# Power.net
KiCad netlist of a schematic drawn in Altium Designer
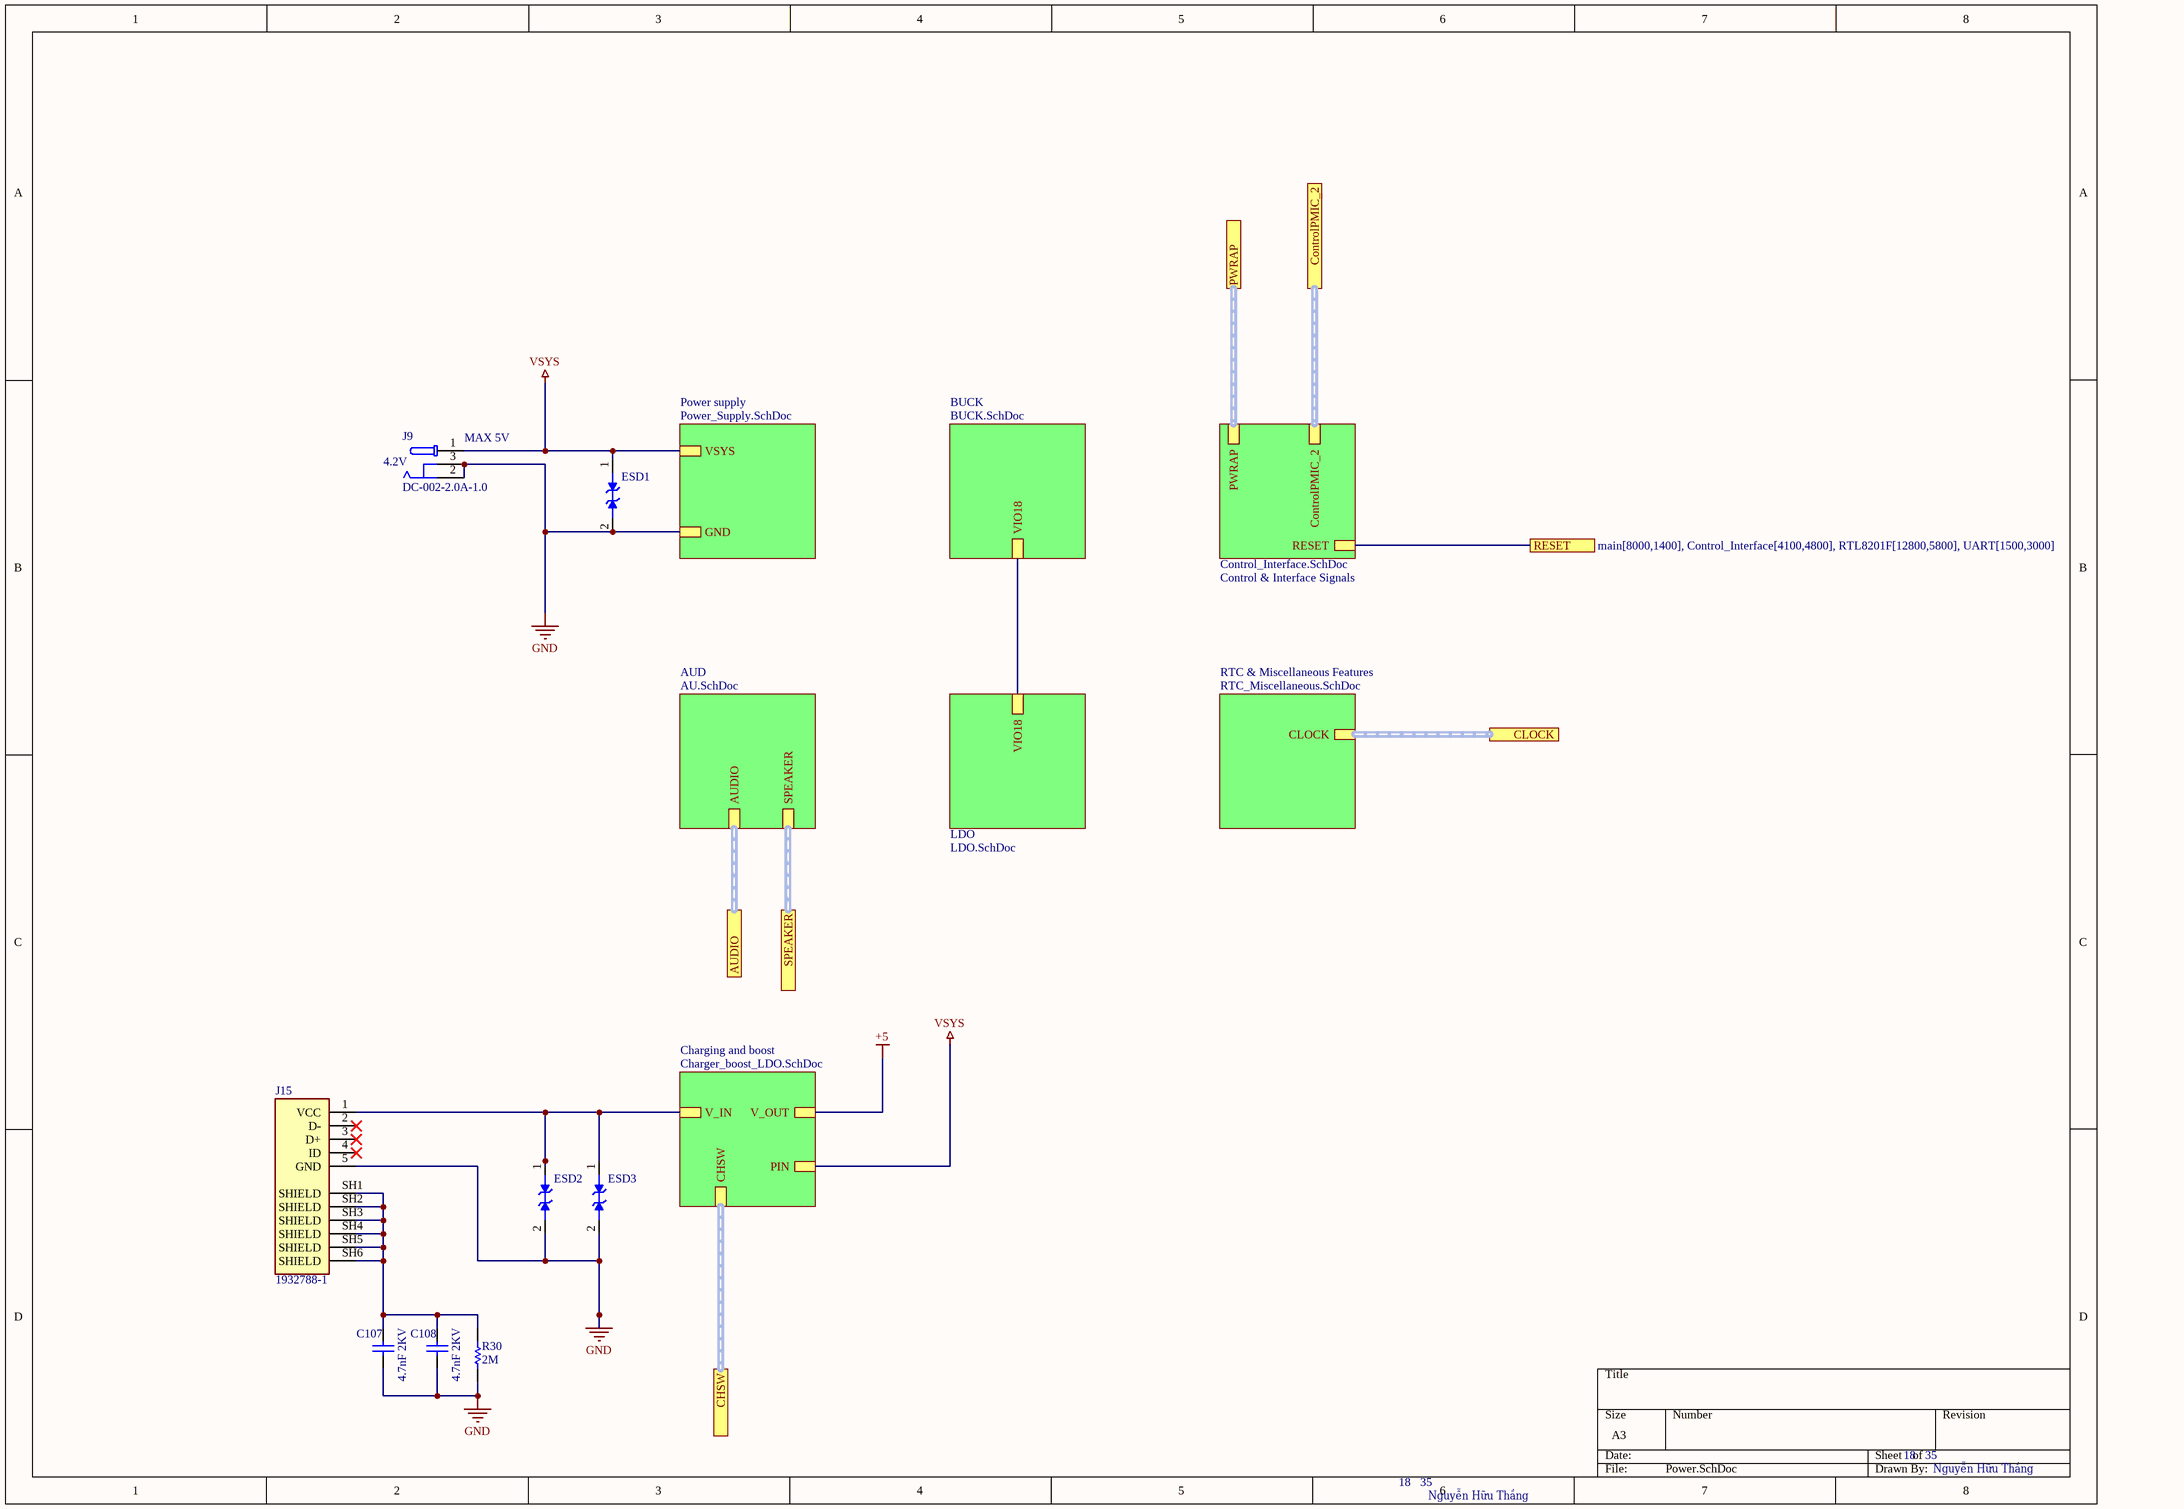
[diagram p0: Power.SchDoc]

(export (version "E")
  (design (tool "Eeschema 10.0.6"))
  (components
    (comp (ref "C107")
      (value "4.7nF 2KV")
      (footprint "C1210")
      (fields (field (name "Comment") "C1210"))
      (libsource (lib "kit") (part "C1210"))
    )
    (comp (ref "C108")
      (value "4.7nF 2KV")
      (footprint "C1210")
      (fields (field (name "Comment") "C1210"))
      (libsource (lib "kit") (part "C1210"))
    )
    (comp (ref "ESD1")
      (value "ESD9B5.0ST5G")
      (footprint "SODFL1006X40N")
      (description "Clamp Ipp Tvs Diode Surface Mount SOD-923")
      (libsource (lib "kit") (part "ESD9B5.0ST5G"))
    )
    (comp (ref "ESD2")
      (value "ESD9B5.0ST5G")
      (footprint "SODFL1006X40N")
      (description "Clamp Ipp Tvs Diode Surface Mount SOD-923")
      (libsource (lib "kit") (part "ESD9B5.0ST5G"))
    )
    (comp (ref "ESD3")
      (value "ESD9B5.0ST5G")
      (footprint "SODFL1006X40N")
      (description "Clamp Ipp Tvs Diode Surface Mount SOD-923")
      (libsource (lib "kit") (part "ESD9B5.0ST5G"))
    )
    (comp (ref "J9")
      (value "DC-002-2.0A-1.0")
      (footprint "DC00220A10")
      (description "Connector")
      (libsource (lib "kit") (part "DC-002-2.0A-1.0"))
    )
    (comp (ref "J15")
      (value "1932788-1")
      (footprint "TE_1932788-1")
      (libsource (lib "kit") (part "1932788-1"))
    )
    (comp (ref "R30")
      (value "2M")
      (footprint "R0603")
      (fields (field (name "Comment") "R0603"))
      (libsource (lib "kit") (part "R0603"))
    )
  )
  (nets
    (net (code "13") (name "/V_IN") (class "Default")
      (node (ref "ESD2") (pin "1") (pinfunction "A_1") (pintype "passive"))
      (node (ref "ESD3") (pin "1") (pinfunction "A_1") (pintype "passive"))
      (node (ref "J15") (pin "1") (pinfunction "VCC_1") (pintype "power_in"))
    )
    (net (code "14") (name "GND") (class "Default")
      (node (ref "C107") (pin "1") (pinfunction "1_1") (pintype "passive"))
      (node (ref "C108") (pin "1") (pinfunction "1_1") (pintype "passive"))
      (node (ref "ESD1") (pin "2") (pinfunction "A1_2") (pintype "passive"))
      (node (ref "ESD2") (pin "2") (pinfunction "A1_2") (pintype "passive"))
      (node (ref "ESD3") (pin "2") (pinfunction "A1_2") (pintype "passive"))
      (node (ref "J15") (pin "5") (pinfunction "GND_5") (pintype "power_in"))
      (node (ref "J9") (pin "2") (pinfunction "2_2") (pintype "passive"))
      (node (ref "J9") (pin "3") (pinfunction "3_3") (pintype "passive"))
      (node (ref "R30") (pin "2") (pinfunction "2_2") (pintype "passive"))
    )
    (net (code "15") (name "Net-(C107-Pad2)") (class "Default")
      (node (ref "C107") (pin "2") (pinfunction "2_2") (pintype "passive"))
      (node (ref "C108") (pin "2") (pinfunction "2_2") (pintype "passive"))
      (node (ref "J15") (pin "SH1") (pinfunction "SHIELD_SH1") (pintype "passive"))
      (node (ref "J15") (pin "SH2") (pinfunction "SHIELD_SH2") (pintype "passive"))
      (node (ref "J15") (pin "SH3") (pinfunction "SHIELD_SH3") (pintype "passive"))
      (node (ref "J15") (pin "SH4") (pinfunction "SHIELD_SH4") (pintype "passive"))
      (node (ref "J15") (pin "SH5") (pinfunction "SHIELD_SH5") (pintype "passive"))
      (node (ref "J15") (pin "SH6") (pinfunction "SHIELD_SH6") (pintype "passive"))
      (node (ref "R30") (pin "1") (pinfunction "1_1") (pintype "passive"))
    )
    (net (code "16") (name "VSYS") (class "Default")
      (node (ref "ESD1") (pin "1") (pinfunction "A_1") (pintype "passive"))
      (node (ref "J9") (pin "1") (pinfunction "1_1") (pintype "passive"))
    )
    (net (code "17") (name "unconnected-(J15-D+-Pad3)") (class "Default")
      (node (ref "J15") (pin "3") (pinfunction "D+_3") (pintype "passive+no_connect"))
    )
    (net (code "18") (name "unconnected-(J15-D--Pad2)") (class "Default")
      (node (ref "J15") (pin "2") (pinfunction "D-_2") (pintype "passive+no_connect"))
    )
    (net (code "19") (name "unconnected-(J15-ID-Pad4)") (class "Default")
      (node (ref "J15") (pin "4") (pinfunction "ID_4") (pintype "passive+no_connect"))
    )
  )
)
